# MyoWare_LED_Shield.net
KiCad netlist of a schematic drawn in EAGLE
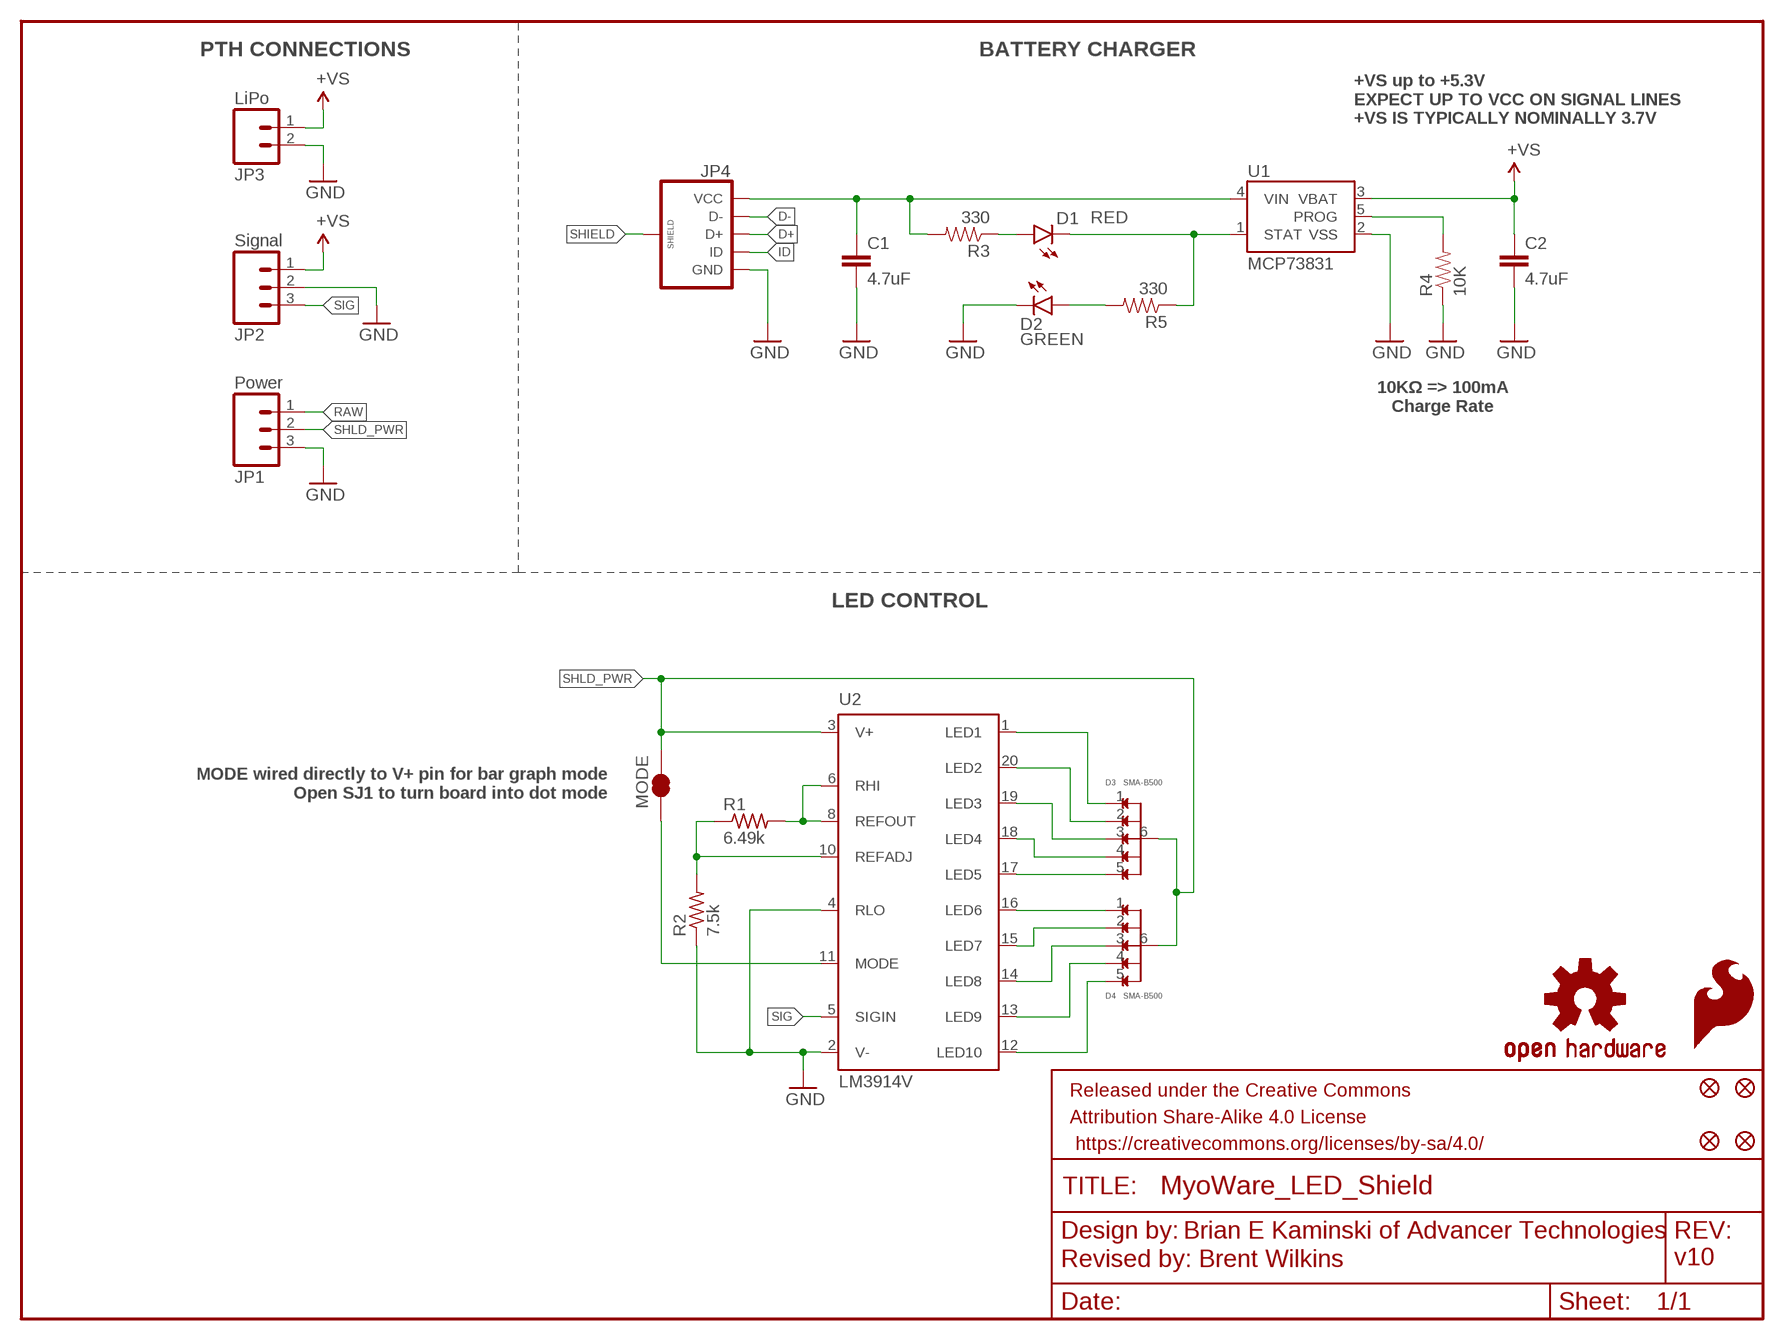
[diagram p0: schematic, sheet 1]

(export (version "E")
  (design (tool "Eeschema 10.0.6"))
  (components
    (comp (ref "C1")
      (value "4.7uF")
      (footprint "eagle-import:0603-CAP")
      (libsource (lib "eagle-import") (part "4.7UF-6.3V-10%(0603)0603"))
    )
    (comp (ref "C2")
      (value "4.7uF")
      (footprint "eagle-import:0603-CAP")
      (libsource (lib "eagle-import") (part "4.7UF-6.3V-10%(0603)0603"))
    )
    (comp (ref "D1")
      (value "RED")
      (footprint "eagle-import:LED-0603")
      (libsource (lib "eagle-import") (part "LED-RED0603"))
    )
    (comp (ref "D2")
      (value "GREEN")
      (footprint "eagle-import:LED-0603")
      (libsource (lib "eagle-import") (part "LED-GREEN0603"))
    )
    (comp (ref "D3")
      (value "SMA-B500")
      (footprint "eagle-import:LED_BAR_SMD")
      (libsource (lib "eagle-import") (part "SMA-B500"))
    )
    (comp (ref "D4")
      (value "SMA-B500")
      (footprint "eagle-import:LED_BAR_SMD")
      (libsource (lib "eagle-import") (part "SMA-B500"))
    )
    (comp (ref "FID1")
      (value "FIDUCIAL1X2")
      (footprint "eagle-import:FIDUCIAL-1X2")
      (libsource (lib "eagle-import") (part "FIDUCIAL1X2"))
    )
    (comp (ref "FID2")
      (value "FIDUCIAL1X2")
      (footprint "eagle-import:FIDUCIAL-1X2")
      (libsource (lib "eagle-import") (part "FIDUCIAL1X2"))
    )
    (comp (ref "FID3")
      (value "FIDUCIAL1X2")
      (footprint "eagle-import:FIDUCIAL-1X2")
      (libsource (lib "eagle-import") (part "FIDUCIAL1X2"))
    )
    (comp (ref "FID4")
      (value "FIDUCIAL1X2")
      (footprint "eagle-import:FIDUCIAL-1X2")
      (libsource (lib "eagle-import") (part "FIDUCIAL1X2"))
    )
    (comp (ref "FRAME1")
      (value "FRAME-LETTER")
      (footprint "eagle-import:CREATIVE_COMMONS")
      (libsource (lib "eagle-import") (part "FRAME-LETTER"))
    )
    (comp (ref "JP1")
      (value "Power")
      (footprint "eagle-import:1X03_NO_SILK")
      (libsource (lib "eagle-import") (part "M031X03_NO_SILK"))
    )
    (comp (ref "JP2")
      (value "Signal")
      (footprint "eagle-import:1X03_NO_SILK")
      (libsource (lib "eagle-import") (part "M031X03_NO_SILK"))
    )
    (comp (ref "JP3")
      (value "LiPo")
      (footprint "eagle-import:1X02_NO_SILK")
      (libsource (lib "eagle-import") (part "M021X02_NO_SILK"))
    )
    (comp (ref "JP4")
      (value "USB_MICROB_PLUGCONN-11752")
      (footprint "eagle-import:USB-B-MICRO-SMD_V03")
      (libsource (lib "eagle-import") (part "USB_MICROB_PLUGCONN-11752"))
    )
    (comp (ref "LOGO1")
      (value "SFE_LOGO_FLAME.1_INCH")
      (footprint "eagle-import:SFE_LOGO_FLAME_.1")
      (libsource (lib "eagle-import") (part "SFE_LOGO_FLAME.1_INCH"))
    )
    (comp (ref "LOGO2")
      (value "OSHW-LOGOS")
      (footprint "eagle-import:OSHW-LOGO-S")
      (libsource (lib "eagle-import") (part "OSHW-LOGOS"))
    )
    (comp (ref "MODE")
      (value "JUMPER-PAD-2-NC_BY_TRACE")
      (footprint "eagle-import:PAD-JUMPER-2-NC_BY_TRACE_YES_SILK")
      (libsource (lib "eagle-import") (part "JUMPER-PAD-2-NC_BY_TRACE"))
    )
    (comp (ref "R1")
      (value "6.49k")
      (footprint "eagle-import:R0603")
      (libsource (lib "eagle-import") (part "R-US_R0603"))
    )
    (comp (ref "R2")
      (value "7.5k")
      (footprint "eagle-import:R0603")
      (libsource (lib "eagle-import") (part "R-US_R0603"))
    )
    (comp (ref "R3")
      (value "330")
      (footprint "eagle-import:0603-RES")
      (libsource (lib "eagle-import") (part "330OHM1/10W1%(0603)"))
    )
    (comp (ref "R4")
      (value "10K")
      (footprint "eagle-import:0603-RES")
      (libsource (lib "eagle-import") (part "10KOHM-1/10W-1%(0603)0603"))
    )
    (comp (ref "R5")
      (value "330")
      (footprint "eagle-import:0603-RES")
      (libsource (lib "eagle-import") (part "330OHM1/10W1%(0603)"))
    )
    (comp (ref "U1")
      (value "MCP73831")
      (footprint "eagle-import:SOT23-5")
      (libsource (lib "eagle-import") (part "MCP73831"))
    )
    (comp (ref "U2")
      (value "LM3914V")
      (footprint "eagle-import:PLCC20S")
      (libsource (lib "eagle-import") (part "LM391V4"))
    )
  )
  (nets
    (net (code "1") (name "+VS") (class "Default")
      (node (ref "C2") (pin "1") (pinfunction "1_1") (pintype "passive"))
      (node (ref "JP2") (pin "1") (pinfunction "1_1") (pintype "passive"))
      (node (ref "JP3") (pin "1") (pinfunction "1_1") (pintype "passive"))
      (node (ref "U1") (pin "3") (pinfunction "VBAT_3") (pintype "power_in"))
    )
    (net (code "2") (name "D+") (class "Default")
      (node (ref "JP4") (pin "D+") (pinfunction "D+_D+") (pintype "bidirectional"))
    )
    (net (code "3") (name "D-") (class "Default")
      (node (ref "JP4") (pin "D-") (pinfunction "D-_D-") (pintype "bidirectional"))
    )
    (net (code "4") (name "GND") (class "Default")
      (node (ref "C1") (pin "2") (pinfunction "2_2") (pintype "passive"))
      (node (ref "C2") (pin "2") (pinfunction "2_2") (pintype "passive"))
      (node (ref "D2") (pin "C") (pinfunction "C_C") (pintype "passive"))
      (node (ref "JP1") (pin "3") (pinfunction "3_3") (pintype "passive"))
      (node (ref "JP2") (pin "2") (pinfunction "2_2") (pintype "passive"))
      (node (ref "JP3") (pin "2") (pinfunction "2_2") (pintype "passive"))
      (node (ref "JP4") (pin "GND") (pinfunction "GND_GND") (pintype "bidirectional"))
      (node (ref "R2") (pin "1") (pinfunction "1_1") (pintype "passive"))
      (node (ref "R4") (pin "1") (pinfunction "1_1") (pintype "passive"))
      (node (ref "U1") (pin "2") (pinfunction "VSS_2") (pintype "power_in"))
      (node (ref "U2") (pin "2") (pinfunction "V-_2") (pintype "power_in"))
      (node (ref "U2") (pin "4") (pinfunction "RLO_4") (pintype "input"))
    )
    (net (code "5") (name "ID") (class "Default")
      (node (ref "JP4") (pin "ID") (pinfunction "ID_ID") (pintype "bidirectional"))
    )
    (net (code "6") (name "Net-(D1-PadA)") (class "Default")
      (node (ref "D1") (pin "A") (pinfunction "A_A") (pintype "passive"))
      (node (ref "R3") (pin "1") (pinfunction "1_1") (pintype "passive"))
    )
    (net (code "7") (name "Net-(D2-PadA)") (class "Default")
      (node (ref "D2") (pin "A") (pinfunction "A_A") (pintype "passive"))
      (node (ref "R5") (pin "2") (pinfunction "2_2") (pintype "passive"))
    )
    (net (code "8") (name "Net-(JP4-VCC)") (class "Default")
      (node (ref "C1") (pin "1") (pinfunction "1_1") (pintype "passive"))
      (node (ref "JP4") (pin "VBUS") (pinfunction "VCC_VBUS") (pintype "bidirectional"))
      (node (ref "R3") (pin "2") (pinfunction "2_2") (pintype "passive"))
      (node (ref "U1") (pin "4") (pinfunction "VIN_4") (pintype "power_in"))
    )
    (net (code "9") (name "Net-(U1-PROG)") (class "Default")
      (node (ref "R4") (pin "2") (pinfunction "2_2") (pintype "passive"))
      (node (ref "U1") (pin "5") (pinfunction "PROG_5") (pintype "input"))
    )
    (net (code "10") (name "Net-(U1-STAT)") (class "Default")
      (node (ref "D1") (pin "C") (pinfunction "C_C") (pintype "passive"))
      (node (ref "R5") (pin "1") (pinfunction "1_1") (pintype "passive"))
      (node (ref "U1") (pin "1") (pinfunction "STAT_1") (pintype "output"))
    )
    (net (code "11") (name "Net-(U2-LED1)") (class "Default")
      (node (ref "D3") (pin "1") (pinfunction "1_1") (pintype "bidirectional"))
      (node (ref "U2") (pin "1") (pinfunction "LED1_1") (pintype "output"))
    )
    (net (code "12") (name "Net-(U2-LED2)") (class "Default")
      (node (ref "D3") (pin "2") (pinfunction "2_2") (pintype "bidirectional"))
      (node (ref "U2") (pin "20") (pinfunction "LED2_20") (pintype "output"))
    )
    (net (code "13") (name "Net-(U2-LED3)") (class "Default")
      (node (ref "D3") (pin "3") (pinfunction "3_3") (pintype "bidirectional"))
      (node (ref "U2") (pin "19") (pinfunction "LED3_19") (pintype "output"))
    )
    (net (code "14") (name "Net-(U2-LED4)") (class "Default")
      (node (ref "D3") (pin "4") (pinfunction "4_4") (pintype "bidirectional"))
      (node (ref "U2") (pin "18") (pinfunction "LED4_18") (pintype "output"))
    )
    (net (code "15") (name "Net-(U2-LED5)") (class "Default")
      (node (ref "D3") (pin "5") (pinfunction "5_5") (pintype "bidirectional"))
      (node (ref "U2") (pin "17") (pinfunction "LED5_17") (pintype "output"))
    )
    (net (code "16") (name "Net-(U2-LED6)") (class "Default")
      (node (ref "D4") (pin "1") (pinfunction "1_1") (pintype "bidirectional"))
      (node (ref "U2") (pin "16") (pinfunction "LED6_16") (pintype "output"))
    )
    (net (code "17") (name "Net-(U2-LED7)") (class "Default")
      (node (ref "D4") (pin "2") (pinfunction "2_2") (pintype "bidirectional"))
      (node (ref "U2") (pin "15") (pinfunction "LED7_15") (pintype "output"))
    )
    (net (code "18") (name "Net-(U2-LED8)") (class "Default")
      (node (ref "D4") (pin "3") (pinfunction "3_3") (pintype "bidirectional"))
      (node (ref "U2") (pin "14") (pinfunction "LED8_14") (pintype "output"))
    )
    (net (code "19") (name "Net-(U2-LED9)") (class "Default")
      (node (ref "D4") (pin "4") (pinfunction "4_4") (pintype "bidirectional"))
      (node (ref "U2") (pin "13") (pinfunction "LED9_13") (pintype "output"))
    )
    (net (code "20") (name "Net-(U2-LED10)") (class "Default")
      (node (ref "D4") (pin "5") (pinfunction "5_5") (pintype "bidirectional"))
      (node (ref "U2") (pin "12") (pinfunction "LED10_12") (pintype "output"))
    )
    (net (code "21") (name "Net-(U2-MODE)") (class "Default")
      (node (ref "MODE") (pin "1") (pinfunction "1_1") (pintype "passive"))
      (node (ref "U2") (pin "11") (pinfunction "MODE_11") (pintype "input"))
    )
    (net (code "22") (name "Net-(U2-REFADJ)") (class "Default")
      (node (ref "R1") (pin "1") (pinfunction "1_1") (pintype "passive"))
      (node (ref "R2") (pin "2") (pinfunction "2_2") (pintype "passive"))
      (node (ref "U2") (pin "10") (pinfunction "REFADJ_10") (pintype "passive"))
    )
    (net (code "23") (name "Net-(U2-REFOUT)") (class "Default")
      (node (ref "R1") (pin "2") (pinfunction "2_2") (pintype "passive"))
      (node (ref "U2") (pin "6") (pinfunction "RHI_6") (pintype "input"))
      (node (ref "U2") (pin "8") (pinfunction "REFOUT_8") (pintype "output"))
    )
    (net (code "24") (name "RAW") (class "Default")
      (node (ref "JP1") (pin "1") (pinfunction "1_1") (pintype "passive"))
    )
    (net (code "25") (name "SHIELD") (class "Default")
      (node (ref "JP4") (pin "SHIELD1") (pinfunction "SHIELD_SHIELD1") (pintype "bidirectional"))
      (node (ref "JP4") (pin "SHIELD2") (pinfunction "SHIELD_SHIELD2") (pintype "bidirectional"))
      (node (ref "JP4") (pin "SHIELD3") (pinfunction "SHIELD_SHIELD3") (pintype "bidirectional"))
    )
    (net (code "26") (name "SHLD_PWR") (class "Default")
      (node (ref "D3") (pin "6") (pinfunction "6_6") (pintype "bidirectional"))
      (node (ref "D4") (pin "6") (pinfunction "6_6") (pintype "bidirectional"))
      (node (ref "JP1") (pin "2") (pinfunction "2_2") (pintype "passive"))
      (node (ref "MODE") (pin "2") (pinfunction "2_2") (pintype "passive"))
      (node (ref "U2") (pin "3") (pinfunction "V+_3") (pintype "power_in"))
    )
    (net (code "27") (name "SIG") (class "Default")
      (node (ref "JP2") (pin "3") (pinfunction "3_3") (pintype "passive"))
      (node (ref "U2") (pin "5") (pinfunction "SIGIN_5") (pintype "input"))
    )
  )
)
